# SmartIMU_I2C_Sch.net
KiCad netlist of a schematic drawn in Altium Designer
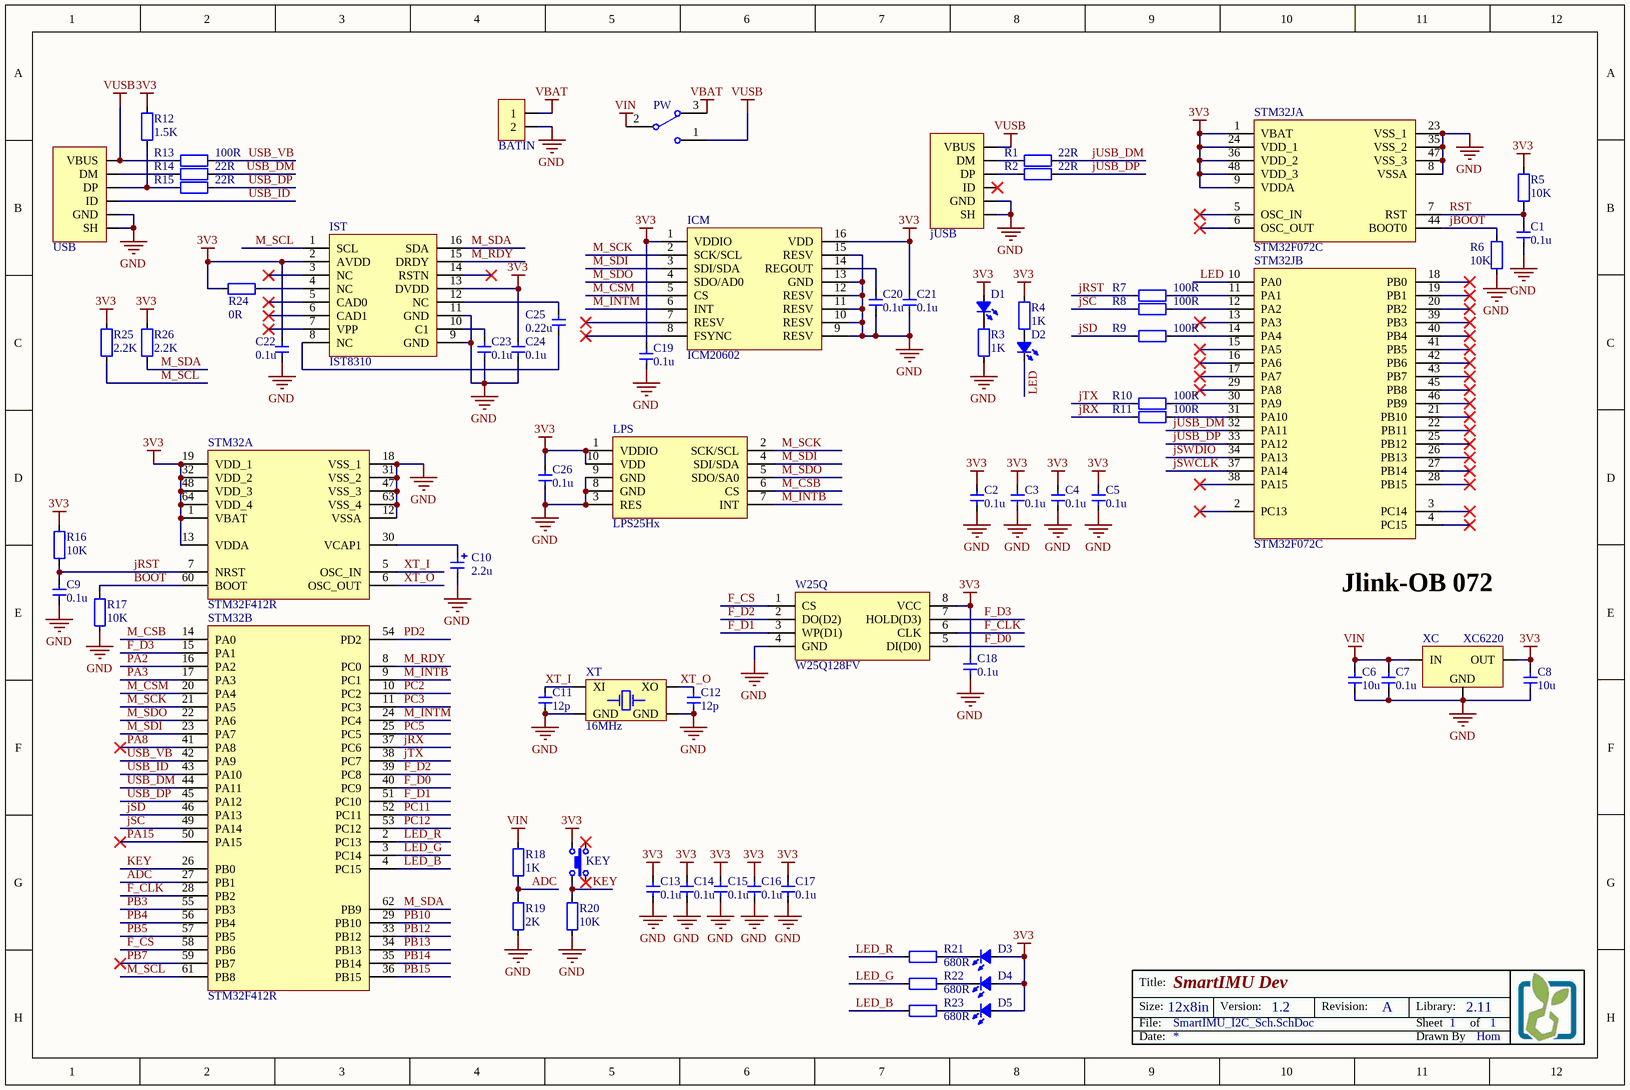
[diagram p0: SmartIMU_I2C_Sch.SchDoc]

(export (version "E")
  (design (tool "Eeschema 10.0.6"))
  (components
    (comp (ref "BATIN")
      (value "MX1.25_2P")
      (footprint "PCB_Connector:MX1.25_S90_2P")
      (description "MX")
      (libsource (lib "SCH_Connector") (part "MX1.25_2P"))
    )
    (comp (ref "C1")
      (value "0.1u")
      (footprint "PCB_PassiveCap:CAP_0603")
      (description "Capacitor")
      (fields (field (name "Comment") "Cap_0603"))
      (libsource (lib "SCH_Passive") (part "Cap_0603"))
    )
    (comp (ref "C2")
      (value "0.1u")
      (footprint "PCB_PassiveCap:CAP_0603")
      (description "Capacitor")
      (fields (field (name "Comment") "Cap_0603"))
      (libsource (lib "SCH_Passive") (part "Cap_0603"))
    )
    (comp (ref "C3")
      (value "0.1u")
      (footprint "PCB_PassiveCap:CAP_0603")
      (description "Capacitor")
      (fields (field (name "Comment") "Cap_0603"))
      (libsource (lib "SCH_Passive") (part "Cap_0603"))
    )
    (comp (ref "C4")
      (value "0.1u")
      (footprint "PCB_PassiveCap:CAP_0603")
      (description "Capacitor")
      (fields (field (name "Comment") "Cap_0603"))
      (libsource (lib "SCH_Passive") (part "Cap_0603"))
    )
    (comp (ref "C5")
      (value "0.1u")
      (footprint "PCB_PassiveCap:CAP_0603")
      (description "Capacitor")
      (fields (field (name "Comment") "Cap_0603"))
      (libsource (lib "SCH_Passive") (part "Cap_0603"))
    )
    (comp (ref "C6")
      (value "10u")
      (footprint "PCB_PassiveCap:CAP_0603")
      (description "Capacitor")
      (fields (field (name "Comment") "Cap_0603"))
      (libsource (lib "SCH_Passive") (part "Cap_0603"))
    )
    (comp (ref "C7")
      (value "0.1u")
      (footprint "PCB_PassiveCap:CAP_0603")
      (description "Capacitor")
      (fields (field (name "Comment") "Cap_0603"))
      (libsource (lib "SCH_Passive") (part "Cap_0603"))
    )
    (comp (ref "C8")
      (value "10u")
      (footprint "PCB_PassiveCap:CAP_0603")
      (description "Capacitor")
      (fields (field (name "Comment") "Cap_0603"))
      (libsource (lib "SCH_Passive") (part "Cap_0603"))
    )
    (comp (ref "C9")
      (value "0.1u")
      (footprint "PCB_PassiveCap:CAP_0603")
      (description "Capacitor")
      (fields (field (name "Comment") "Cap_0603"))
      (libsource (lib "SCH_Passive") (part "Cap_0603"))
    )
    (comp (ref "C10")
      (value "2.2u")
      (footprint "PCB_PassiveCap:CAP_TAN_P0805")
      (description "Capacitor")
      (fields (field (name "Comment") "Cap_Tan_0805"))
      (libsource (lib "SCH_Passive") (part "Cap_Tan_0805"))
    )
    (comp (ref "C11")
      (value "12p")
      (footprint "PCB_PassiveCap:CAP_0603")
      (description "Capacitor")
      (fields (field (name "Comment") "Cap_0603"))
      (libsource (lib "SCH_Passive") (part "Cap_0603"))
    )
    (comp (ref "C12")
      (value "12p")
      (footprint "PCB_PassiveCap:CAP_0603")
      (description "Capacitor")
      (fields (field (name "Comment") "Cap_0603"))
      (libsource (lib "SCH_Passive") (part "Cap_0603"))
    )
    (comp (ref "C13")
      (value "0.1u")
      (footprint "PCB_PassiveCap:CAP_0603")
      (description "Capacitor")
      (fields (field (name "Comment") "Cap_0603"))
      (libsource (lib "SCH_Passive") (part "Cap_0603"))
    )
    (comp (ref "C14")
      (value "0.1u")
      (footprint "PCB_PassiveCap:CAP_0603")
      (description "Capacitor")
      (fields (field (name "Comment") "Cap_0603"))
      (libsource (lib "SCH_Passive") (part "Cap_0603"))
    )
    (comp (ref "C15")
      (value "0.1u")
      (footprint "PCB_PassiveCap:CAP_0603")
      (description "Capacitor")
      (fields (field (name "Comment") "Cap_0603"))
      (libsource (lib "SCH_Passive") (part "Cap_0603"))
    )
    (comp (ref "C16")
      (value "0.1u")
      (footprint "PCB_PassiveCap:CAP_0603")
      (description "Capacitor")
      (fields (field (name "Comment") "Cap_0603"))
      (libsource (lib "SCH_Passive") (part "Cap_0603"))
    )
    (comp (ref "C17")
      (value "0.1u")
      (footprint "PCB_PassiveCap:CAP_0603")
      (description "Capacitor")
      (fields (field (name "Comment") "Cap_0603"))
      (libsource (lib "SCH_Passive") (part "Cap_0603"))
    )
    (comp (ref "C18")
      (value "0.1u")
      (footprint "PCB_PassiveCap:CAP_0603")
      (description "Capacitor")
      (fields (field (name "Comment") "Cap_0603"))
      (libsource (lib "SCH_Passive") (part "Cap_0603"))
    )
    (comp (ref "C19")
      (value "0.1u")
      (footprint "PCB_PassiveCap:CAP_0603")
      (description "Capacitor")
      (fields (field (name "Comment") "Cap_0603"))
      (libsource (lib "SCH_Passive") (part "Cap_0603"))
    )
    (comp (ref "C20")
      (value "0.1u")
      (footprint "PCB_PassiveCap:CAP_0603")
      (description "Capacitor")
      (fields (field (name "Comment") "Cap_0603"))
      (libsource (lib "SCH_Passive") (part "Cap_0603"))
    )
    (comp (ref "C21")
      (value "0.1u")
      (footprint "PCB_PassiveCap:CAP_0603")
      (description "Capacitor")
      (fields (field (name "Comment") "Cap_0603"))
      (libsource (lib "SCH_Passive") (part "Cap_0603"))
    )
    (comp (ref "C22")
      (value "0.1u")
      (footprint "PCB_PassiveCap:CAP_0603")
      (description "Capacitor")
      (fields (field (name "Comment") "Cap_0603"))
      (libsource (lib "SCH_Passive") (part "Cap_0603"))
    )
    (comp (ref "C23")
      (value "0.1u")
      (footprint "PCB_PassiveCap:CAP_0603")
      (description "Capacitor")
      (fields (field (name "Comment") "Cap_0603"))
      (libsource (lib "SCH_Passive") (part "Cap_0603"))
    )
    (comp (ref "C24")
      (value "0.1u")
      (footprint "PCB_PassiveCap:CAP_0603")
      (description "Capacitor")
      (fields (field (name "Comment") "Cap_0603"))
      (libsource (lib "SCH_Passive") (part "Cap_0603"))
    )
    (comp (ref "C25")
      (value "0.22u")
      (footprint "PCB_PassiveCap:CAP_0603")
      (description "Capacitor")
      (fields (field (name "Comment") "Cap_0603"))
      (libsource (lib "SCH_Passive") (part "Cap_0603"))
    )
    (comp (ref "C26")
      (value "0.1u")
      (footprint "PCB_PassiveCap:CAP_0603")
      (description "Capacitor")
      (fields (field (name "Comment") "Cap_0603"))
      (libsource (lib "SCH_Passive") (part "Cap_0603"))
    )
    (comp (ref "D1")
      (value "LED_0603")
      (footprint "PCB_ActiveLED:LED_0603_YELLOW")
      (description "LED")
      (libsource (lib "SCH_Active") (part "LED_0603"))
    )
    (comp (ref "D2")
      (value "LED_0603")
      (footprint "PCB_ActiveLED:LED_0603_ORANGE")
      (description "LED")
      (libsource (lib "SCH_Active") (part "LED_0603"))
    )
    (comp (ref "D3")
      (value "LED_0603")
      (footprint "PCB_ActiveLED:LED_0603_RED")
      (description "LED")
      (libsource (lib "SCH_Active") (part "LED_0603"))
    )
    (comp (ref "D4")
      (value "LED_0603")
      (footprint "PCB_ActiveLED:LED_0603_GREEN")
      (description "LED")
      (libsource (lib "SCH_Active") (part "LED_0603"))
    )
    (comp (ref "D5")
      (value "LED_0603")
      (footprint "PCB_ActiveLED:LED_0603_BLUE")
      (description "LED")
      (libsource (lib "SCH_Active") (part "LED_0603"))
    )
    (comp (ref "ICM")
      (value "ICM20602")
      (footprint "LGA_P0.5_16")
      (description "Sensor Motion")
      (libsource (lib "SCH_IntegratedCircuit") (part "ICM20602"))
    )
    (comp (ref "IST")
      (value "IST8310")
      (footprint "PCB_IntegratedCircuit:QFN_P0.5_16")
      (description "Sensor Magnetometer")
      (libsource (lib "SCH_IntegratedCircuit") (part "IST8310"))
    )
    (comp (ref "jUSB")
      (value "USB_Micro")
      (footprint "PCB_USB:USB_Micro-AB")
      (description "USB")
      (libsource (lib "SCH_USB") (part "USB_Micro"))
    )
    (comp (ref "KEY")
      (value "ButtonTACT")
      (footprint "PCB_Switch:ButtonTACT_3.5*3.55_90")
      (description "Button")
      (libsource (lib "SCH_Switch") (part "ButtonTACT"))
    )
    (comp (ref "LPS")
      (value "LPS25Hx")
      (footprint "PCB_IntegratedCircuit:HCLGA-2.5x2.5_10")
      (description "Sensor Pressure")
      (libsource (lib "SCH_IntegratedCircuit") (part "LPS25Hx"))
    )
    (comp (ref "PW")
      (value "SwitchSPDT_2.8x6.6_90")
      (footprint "PCB_Switch:SwitchSPDT_2.8X6.6_90")
      (description "Switch")
      (libsource (lib "SCH_Switch") (part "SwitchSPDT_2.8x6.6_90"))
    )
    (comp (ref "R1")
      (value "22R")
      (footprint "PCB_PassiveRes:RES_0603")
      (description "Resistor")
      (fields (field (name "Comment") "Res_0603"))
      (libsource (lib "") (part "Res_0603_2"))
    )
    (comp (ref "R2")
      (value "22R")
      (footprint "PCB_PassiveRes:RES_0603")
      (description "Resistor")
      (fields (field (name "Comment") "Res_0603"))
      (libsource (lib "") (part "Res_0603_2"))
    )
    (comp (ref "R3")
      (value "1K")
      (footprint "PCB_PassiveRes:RES_0603")
      (description "Resistor")
      (fields (field (name "Comment") "Res_0603"))
      (libsource (lib "") (part "Res_0603_3"))
    )
    (comp (ref "R4")
      (value "1K")
      (footprint "PCB_PassiveRes:RES_0603")
      (description "Resistor")
      (fields (field (name "Comment") "Res_0603"))
      (libsource (lib "") (part "Res_0603_3"))
    )
    (comp (ref "R5")
      (value "10K")
      (footprint "PCB_PassiveRes:RES_0603")
      (description "Resistor")
      (fields (field (name "Comment") "Res_0603"))
      (libsource (lib "") (part "Res_0603_3"))
    )
    (comp (ref "R6")
      (value "10K")
      (footprint "PCB_PassiveRes:RES_0603")
      (description "Resistor")
      (fields (field (name "Comment") "Res_0603"))
      (libsource (lib "") (part "Res_0603_3"))
    )
    (comp (ref "R7")
      (value "100R")
      (footprint "PCB_PassiveRes:RES_0603")
      (description "Resistor")
      (fields (field (name "Comment") "Res_0603"))
      (libsource (lib "") (part "Res_0603_2"))
    )
    (comp (ref "R8")
      (value "100R")
      (footprint "PCB_PassiveRes:RES_0603")
      (description "Resistor")
      (fields (field (name "Comment") "Res_0603"))
      (libsource (lib "") (part "Res_0603_2"))
    )
    (comp (ref "R9")
      (value "100R")
      (footprint "PCB_PassiveRes:RES_0603")
      (description "Resistor")
      (fields (field (name "Comment") "Res_0603"))
      (libsource (lib "") (part "Res_0603_2"))
    )
    (comp (ref "R10")
      (value "100R")
      (footprint "PCB_PassiveRes:RES_0603")
      (description "Resistor")
      (fields (field (name "Comment") "Res_0603"))
      (libsource (lib "") (part "Res_0603_2"))
    )
    (comp (ref "R11")
      (value "100R")
      (footprint "PCB_PassiveRes:RES_0603")
      (description "Resistor")
      (fields (field (name "Comment") "Res_0603"))
      (libsource (lib "") (part "Res_0603_2"))
    )
    (comp (ref "R12")
      (value "1.5K")
      (footprint "PCB_PassiveRes:RES_0603")
      (description "Resistor")
      (fields (field (name "Comment") "Res_0603"))
      (libsource (lib "SCH_Passive") (part "Res_0603"))
    )
    (comp (ref "R13")
      (value "100R")
      (footprint "PCB_PassiveRes:RES_0603")
      (description "Resistor")
      (fields (field (name "Comment") "Res_0603"))
      (libsource (lib "") (part "Res_0603_1"))
    )
    (comp (ref "R14")
      (value "22R")
      (footprint "PCB_PassiveRes:RES_0603")
      (description "Resistor")
      (fields (field (name "Comment") "Res_0603"))
      (libsource (lib "") (part "Res_0603_1"))
    )
    (comp (ref "R15")
      (value "22R")
      (footprint "PCB_PassiveRes:RES_0603")
      (description "Resistor")
      (fields (field (name "Comment") "Res_0603"))
      (libsource (lib "") (part "Res_0603_1"))
    )
    (comp (ref "R16")
      (value "10K")
      (footprint "PCB_PassiveRes:RES_0603")
      (description "Resistor")
      (fields (field (name "Comment") "Res_0603"))
      (libsource (lib "") (part "Res_0603_3"))
    )
    (comp (ref "R17")
      (value "10K")
      (footprint "PCB_PassiveRes:RES_0603")
      (description "Resistor")
      (fields (field (name "Comment") "Res_0603"))
      (libsource (lib "") (part "Res_0603_3"))
    )
    (comp (ref "R18")
      (value "1K")
      (footprint "PCB_PassiveRes:RES_0603")
      (description "Resistor")
      (fields (field (name "Comment") "Res_0603"))
      (libsource (lib "SCH_Passive") (part "Res_0603"))
    )
    (comp (ref "R19")
      (value "2K")
      (footprint "PCB_PassiveRes:RES_0603")
      (description "Resistor")
      (fields (field (name "Comment") "Res_0603"))
      (libsource (lib "SCH_Passive") (part "Res_0603"))
    )
    (comp (ref "R20")
      (value "10K")
      (footprint "PCB_PassiveRes:RES_0603")
      (description "Resistor")
      (fields (field (name "Comment") "Res_0603"))
      (libsource (lib "") (part "Res_0603_3"))
    )
    (comp (ref "R21")
      (value "680R")
      (footprint "PCB_PassiveRes:RES_0603")
      (description "Resistor")
      (fields (field (name "Comment") "Res_0603"))
      (libsource (lib "") (part "Res_0603_1"))
    )
    (comp (ref "R22")
      (value "680R")
      (footprint "PCB_PassiveRes:RES_0603")
      (description "Resistor")
      (fields (field (name "Comment") "Res_0603"))
      (libsource (lib "") (part "Res_0603_1"))
    )
    (comp (ref "R23")
      (value "680R")
      (footprint "PCB_PassiveRes:RES_0603")
      (description "Resistor")
      (fields (field (name "Comment") "Res_0603"))
      (libsource (lib "") (part "Res_0603_1"))
    )
    (comp (ref "R24")
      (value "0R")
      (footprint "PCB_PassiveRes:RES_0603")
      (description "Resistor")
      (fields (field (name "Comment") "Res_0603"))
      (libsource (lib "") (part "Res_0603_1"))
    )
    (comp (ref "R25")
      (value "2.2K")
      (footprint "PCB_PassiveRes:RES_0603")
      (description "Resistor")
      (fields (field (name "Comment") "Res_0603"))
      (libsource (lib "SCH_Passive") (part "Res_0603"))
    )
    (comp (ref "R26")
      (value "2.2K")
      (footprint "PCB_PassiveRes:RES_0603")
      (description "Resistor")
      (fields (field (name "Comment") "Res_0603"))
      (libsource (lib "SCH_Passive") (part "Res_0603"))
    )
    (comp (ref "STM32")
      (value "STM32F412R")
      (footprint "PCB_IntegratedCircuit:LQFP_P0.5_64")
      (description "MCU")
      (libsource (lib "SCH_IntegratedCircuit") (part "STM32F412R/446R"))
    )
    (comp (ref "STM32J")
      (value "STM32F072C")
      (footprint "PCB_IntegratedCircuit:LQFP_P0.5_48")
      (description "MCU")
      (libsource (lib "SCH_IntegratedCircuit") (part "STM32F103C"))
    )
    (comp (ref "USB")
      (value "USB_Micro")
      (footprint "PCB_USB:USB_Micro-AB")
      (description "USB")
      (libsource (lib "SCH_USB") (part "USB_Micro"))
    )
    (comp (ref "W25Q")
      (value "W25Q128FV")
      (footprint "PCB_IntegratedCircuit:SON_P1.27H_8")
      (description "FLASH")
      (libsource (lib "SCH_IntegratedCircuit") (part "W25Q_8"))
    )
    (comp (ref "XC")
      (value "XC6220")
      (footprint "PCB_IntegratedCircuit:SOT89-3")
      (description "Power")
      (libsource (lib "SCH_IntegratedCircuit") (part "XC6220"))
    )
    (comp (ref "XT")
      (value "16MHz")
      (footprint "PCB_Oscillator:XT_2520_4")
      (description "Crystal Oscillator")
      (fields (field (name "Comment") "XTAL_2520_4P"))
      (libsource (lib "SCH_Oscillator") (part "XTAL_2520_4P"))
    )
  )
  (nets
    (net (code "1") (name "/ADC") (class "Default")
      (node (ref "R18") (pin "2") (pinfunction "2_2") (pintype "passive"))
      (node (ref "R19") (pin "1") (pinfunction "1_1") (pintype "passive"))
      (node (ref "STM32") (pin "27") (pinfunction "PB1_27") (pintype "passive"))
    )
    (net (code "2") (name "/BOOT") (class "Default")
      (node (ref "R17") (pin "2") (pinfunction "2_2") (pintype "passive"))
      (node (ref "STM32") (pin "60") (pinfunction "BOOT_60") (pintype "passive"))
    )
    (net (code "3") (name "/F_CLK") (class "Default")
      (node (ref "STM32") (pin "28") (pinfunction "PB2_28") (pintype "passive"))
      (node (ref "W25Q") (pin "6") (pinfunction "CLK_6") (pintype "passive"))
    )
    (net (code "4") (name "/F_CS") (class "Default")
      (node (ref "STM32") (pin "58") (pinfunction "PB6_58") (pintype "passive"))
      (node (ref "W25Q") (pin "1") (pinfunction "CS_1") (pintype "passive"))
    )
    (net (code "5") (name "/F_D0") (class "Default")
      (node (ref "STM32") (pin "40") (pinfunction "PC9_40") (pintype "passive"))
      (node (ref "W25Q") (pin "5") (pinfunction "DI(D0)_5") (pintype "passive"))
    )
    (net (code "6") (name "/F_D1") (class "Default")
      (node (ref "STM32") (pin "51") (pinfunction "PC10_51") (pintype "passive"))
      (node (ref "W25Q") (pin "3") (pinfunction "WP(D1)_3") (pintype "passive"))
    )
    (net (code "7") (name "/F_D2") (class "Default")
      (node (ref "STM32") (pin "39") (pinfunction "PC8_39") (pintype "passive"))
      (node (ref "W25Q") (pin "2") (pinfunction "DO(D2)_2") (pintype "passive"))
    )
    (net (code "8") (name "/F_D3") (class "Default")
      (node (ref "STM32") (pin "15") (pinfunction "PA1_15") (pintype "passive"))
      (node (ref "W25Q") (pin "7") (pinfunction "HOLD(D3)_7") (pintype "passive"))
    )
    (net (code "9") (name "/KEY") (class "Default")
      (node (ref "KEY") (pin "1") (pinfunction "1_1") (pintype "passive"))
      (node (ref "R20") (pin "2") (pinfunction "2_2") (pintype "passive"))
      (node (ref "STM32") (pin "26") (pinfunction "PB0_26") (pintype "passive"))
    )
    (net (code "10") (name "/LED") (class "Default")
      (node (ref "D2") (pin "2") (pinfunction "K_2") (pintype "passive"))
      (node (ref "STM32J") (pin "10") (pinfunction "PA0_10") (pintype "passive"))
    )
    (net (code "11") (name "/LED_B") (class "Default")
      (node (ref "R23") (pin "2") (pinfunction "2_2") (pintype "passive"))
      (node (ref "STM32") (pin "4") (pinfunction "PC15_4") (pintype "passive"))
    )
    (net (code "12") (name "/LED_G") (class "Default")
      (node (ref "R22") (pin "2") (pinfunction "2_2") (pintype "passive"))
      (node (ref "STM32") (pin "3") (pinfunction "PC14_3") (pintype "passive"))
    )
    (net (code "13") (name "/LED_R") (class "Default")
      (node (ref "R21") (pin "2") (pinfunction "2_2") (pintype "passive"))
      (node (ref "STM32") (pin "2") (pinfunction "PC13_2") (pintype "passive"))
    )
    (net (code "14") (name "/M_CSB") (class "Default")
      (node (ref "LPS") (pin "6") (pinfunction "CS_6") (pintype "passive"))
      (node (ref "STM32") (pin "14") (pinfunction "PA0_14") (pintype "passive"))
    )
    (net (code "15") (name "/M_CSM") (class "Default")
      (node (ref "ICM") (pin "5") (pinfunction "CS_5") (pintype "passive"))
      (node (ref "STM32") (pin "20") (pinfunction "PA4_20") (pintype "passive"))
    )
    (net (code "16") (name "/M_INTB") (class "Default")
      (node (ref "LPS") (pin "7") (pinfunction "INT_7") (pintype "passive"))
      (node (ref "STM32") (pin "9") (pinfunction "PC1_9") (pintype "passive"))
    )
    (net (code "17") (name "/M_INTM") (class "Default")
      (node (ref "ICM") (pin "6") (pinfunction "INT_6") (pintype "passive"))
      (node (ref "STM32") (pin "24") (pinfunction "PC4_24") (pintype "passive"))
    )
    (net (code "18") (name "/M_RDY") (class "Default")
      (node (ref "IST") (pin "15") (pinfunction "DRDY_15") (pintype "passive"))
      (node (ref "STM32") (pin "8") (pinfunction "PC0_8") (pintype "passive"))
    )
    (net (code "19") (name "/M_SCK") (class "Default")
      (node (ref "ICM") (pin "2") (pinfunction "SCK/SCL_2") (pintype "passive"))
      (node (ref "LPS") (pin "2") (pinfunction "SCK/SCL_2") (pintype "passive"))
      (node (ref "STM32") (pin "21") (pinfunction "PA5_21") (pintype "passive"))
    )
    (net (code "20") (name "/M_SCL") (class "Default")
      (node (ref "IST") (pin "1") (pinfunction "SCL_1") (pintype "passive"))
      (node (ref "R25") (pin "2") (pinfunction "2_2") (pintype "passive"))
      (node (ref "STM32") (pin "61") (pinfunction "PB8_61") (pintype "passive"))
    )
    (net (code "21") (name "/M_SDA") (class "Default")
      (node (ref "IST") (pin "16") (pinfunction "SDA_16") (pintype "passive"))
      (node (ref "R26") (pin "2") (pinfunction "2_2") (pintype "passive"))
      (node (ref "STM32") (pin "62") (pinfunction "PB9_62") (pintype "passive"))
    )
    (net (code "22") (name "/M_SDI") (class "Default")
      (node (ref "ICM") (pin "3") (pinfunction "SDI/SDA_3") (pintype "passive"))
      (node (ref "LPS") (pin "4") (pinfunction "SDI/SDA_4") (pintype "passive"))
      (node (ref "STM32") (pin "23") (pinfunction "PA7_23") (pintype "passive"))
    )
    (net (code "23") (name "/M_SDO") (class "Default")
      (node (ref "ICM") (pin "4") (pinfunction "SDO/AD0_4") (pintype "passive"))
      (node (ref "LPS") (pin "5") (pinfunction "SDO/SA0_5") (pintype "passive"))
      (node (ref "STM32") (pin "22") (pinfunction "PA6_22") (pintype "passive"))
    )
    (net (code "24") (name "/PA2") (class "Default")
      (node (ref "STM32") (pin "16") (pinfunction "PA2_16") (pintype "passive"))
    )
    (net (code "25") (name "/PA3") (class "Default")
      (node (ref "STM32") (pin "17") (pinfunction "PA3_17") (pintype "passive"))
    )
    (net (code "26") (name "/PA8") (class "Default")
      (node (ref "STM32") (pin "41") (pinfunction "PA8_41") (pintype "passive+no_connect"))
    )
    (net (code "27") (name "/PA15") (class "Default")
      (node (ref "STM32") (pin "50") (pinfunction "PA15_50") (pintype "passive+no_connect"))
    )
    (net (code "28") (name "/PB3") (class "Default")
      (node (ref "STM32") (pin "55") (pinfunction "PB3_55") (pintype "passive"))
    )
    (net (code "29") (name "/PB4") (class "Default")
      (node (ref "STM32") (pin "56") (pinfunction "PB4_56") (pintype "passive"))
    )
    (net (code "30") (name "/PB5") (class "Default")
      (node (ref "STM32") (pin "57") (pinfunction "PB5_57") (pintype "passive"))
    )
    (net (code "31") (name "/PB7") (class "Default")
      (node (ref "STM32") (pin "59") (pinfunction "PB7_59") (pintype "passive+no_connect"))
    )
    (net (code "32") (name "/PB10") (class "Default")
      (node (ref "STM32") (pin "29") (pinfunction "PB10_29") (pintype "passive"))
    )
    (net (code "33") (name "/PB12") (class "Default")
      (node (ref "STM32") (pin "33") (pinfunction "PB12_33") (pintype "passive"))
    )
    (net (code "34") (name "/PB13") (class "Default")
      (node (ref "STM32") (pin "34") (pinfunction "PB13_34") (pintype "passive"))
    )
    (net (code "35") (name "/PB14") (class "Default")
      (node (ref "STM32") (pin "35") (pinfunction "PB14_35") (pintype "passive"))
    )
    (net (code "36") (name "/PB15") (class "Default")
      (node (ref "STM32") (pin "36") (pinfunction "PB15_36") (pintype "passive"))
    )
    (net (code "37") (name "/PC2") (class "Default")
      (node (ref "STM32") (pin "10") (pinfunction "PC2_10") (pintype "passive"))
    )
    (net (code "38") (name "/PC3") (class "Default")
      (node (ref "STM32") (pin "11") (pinfunction "PC3_11") (pintype "passive"))
    )
    (net (code "39") (name "/PC5") (class "Default")
      (node (ref "STM32") (pin "25") (pinfunction "PC5_25") (pintype "passive"))
    )
    (net (code "40") (name "/PC11") (class "Default")
      (node (ref "STM32") (pin "52") (pinfunction "PC11_52") (pintype "passive"))
    )
    (net (code "41") (name "/PC12") (class "Default")
      (node (ref "STM32") (pin "53") (pinfunction "PC12_53") (pintype "passive"))
    )
    (net (code "42") (name "/PD2") (class "Default")
      (node (ref "STM32") (pin "54") (pinfunction "PD2_54") (pintype "passive"))
    )
    (net (code "43") (name "/RST") (class "Default")
      (node (ref "C1") (pin "2") (pinfunction "2_2") (pintype "passive"))
      (node (ref "R5") (pin "1") (pinfunction "1_1") (pintype "passive"))
      (node (ref "STM32J") (pin "7") (pinfunction "RST_7") (pintype "passive"))
    )
    (net (code "44") (name "/USB_DM") (class "Default")
      (node (ref "R14") (pin "1") (pinfunction "1_1") (pintype "passive"))
      (node (ref "STM32") (pin "44") (pinfunction "PA11_44") (pintype "passive"))
    )
    (net (code "45") (name "/USB_DP") (class "Default")
      (node (ref "R15") (pin "1") (pinfunction "1_1") (pintype "passive"))
      (node (ref "STM32") (pin "45") (pinfunction "PA12_45") (pintype "passive"))
    )
    (net (code "46") (name "/USB_ID") (class "Default")
      (node (ref "STM32") (pin "43") (pinfunction "PA10_43") (pintype "passive"))
      (node (ref "USB") (pin "4") (pinfunction "ID_4") (pintype "passive"))
    )
    (net (code "47") (name "/USB_VB") (class "Default")
      (node (ref "R13") (pin "1") (pinfunction "1_1") (pintype "passive"))
      (node (ref "STM32") (pin "42") (pinfunction "PA9_42") (pintype "passive"))
    )
    (net (code "48") (name "/XT_I") (class "Default")
      (node (ref "C11") (pin "1") (pinfunction "1_1") (pintype "passive"))
      (node (ref "STM32") (pin "5") (pinfunction "OSC_IN_5") (pintype "passive"))
      (node (ref "XT") (pin "1") (pinfunction "XI_1") (pintype "passive"))
    )
    (net (code "49") (name "/XT_O") (class "Default")
      (node (ref "C12") (pin "1") (pinfunction "1_1") (pintype "passive"))
      (node (ref "STM32") (pin "6") (pinfunction "OSC_OUT_6") (pintype "passive"))
      (node (ref "XT") (pin "3") (pinfunction "XO_3") (pintype "passive"))
    )
    (net (code "50") (name "/jBOOT") (class "Default")
      (node (ref "R6") (pin "2") (pinfunction "2_2") (pintype "passive"))
      (node (ref "STM32J") (pin "44") (pinfunction "BOOT0_44") (pintype "passive"))
    )
    (net (code "51") (name "/jRST") (class "Default")
      (node (ref "C9") (pin "2") (pinfunction "2_2") (pintype "passive"))
      (node (ref "R16") (pin "1") (pinfunction "1_1") (pintype "passive"))
      (node (ref "R7") (pin "1") (pinfunction "1_1") (pintype "passive"))
      (node (ref "STM32") (pin "7") (pinfunction "NRST_7") (pintype "passive"))
    )
    (net (code "52") (name "/jRX") (class "Default")
      (node (ref "R11") (pin "1") (pinfunction "1_1") (pintype "passive"))
      (node (ref "STM32") (pin "37") (pinfunction "PC6_37") (pintype "passive"))
    )
    (net (code "53") (name "/jSC") (class "Default")
      (node (ref "R8") (pin "1") (pinfunction "1_1") (pintype "passive"))
      (node (ref "STM32") (pin "49") (pinfunction "PA14_49") (pintype "passive"))
    )
    (net (code "54") (name "/jSD") (class "Default")
      (node (ref "R9") (pin "1") (pinfunction "1_1") (pintype "passive"))
      (node (ref "STM32") (pin "46") (pinfunction "PA13_46") (pintype "passive"))
    )
    (net (code "55") (name "/jSWCLK") (class "Default")
      (node (ref "STM32J") (pin "37") (pinfunction "PA14_37") (pintype "passive"))
    )
    (net (code "56") (name "/jSWDIO") (class "Default")
      (node (ref "STM32J") (pin "34") (pinfunction "PA13_34") (pintype "passive"))
    )
    (net (code "57") (name "/jTX") (class "Default")
      (node (ref "R10") (pin "1") (pinfunction "1_1") (pintype "passive"))
      (node (ref "STM32") (pin "38") (pinfunction "PC7_38") (pintype "passive"))
    )
    (net (code "58") (name "/jUSB_DM") (class "Default")
      (node (ref "R1") (pin "2") (pinfunction "2_2") (pintype "passive"))
      (node (ref "STM32J") (pin "32") (pinfunction "PA11_32") (pintype "passive"))
    )
    (net (code "59") (name "/jUSB_DP") (class "Default")
      (node (ref "R2") (pin "2") (pinfunction "2_2") (pintype "passive"))
      (node (ref "STM32J") (pin "33") (pinfunction "PA12_33") (pintype "passive"))
    )
    (net (code "60") (name "3V3") (class "Default")
      (node (ref "C13") (pin "1") (pinfunction "1_1") (pintype "passive"))
      (node (ref "C14") (pin "1") (pinfunction "1_1") (pintype "passive"))
      (node (ref "C15") (pin "1") (pinfunction "1_1") (pintype "passive"))
      (node (ref "C16") (pin "1") (pinfunction "1_1") (pintype "passive"))
      (node (ref "C17") (pin "2") (pinfunction "2_2") (pintype "passive"))
      (node (ref "C18") (pin "1") (pinfunction "1_1") (pintype "passive"))
      (node (ref "C19") (pin "1") (pinfunction "1_1") (pintype "passive"))
      (node (ref "C2") (pin "2") (pinfunction "2_2") (pintype "passive"))
      (node (ref "C21") (pin "1") (pinfunction "1_1") (pintype "passive"))
      (node (ref "C22") (pin "1") (pinfunction "1_1") (pintype "passive"))
      (node (ref "C24") (pin "1") (pinfunction "1_1") (pintype "passive"))
      (node (ref "C26") (pin "1") (pinfunction "1_1") (pintype "passive"))
      (node (ref "C3") (pin "2") (pinfunction "2_2") (pintype "passive"))
      (node (ref "C4") (pin "2") (pinfunction "2_2") (pintype "passive"))
      (node (ref "C5") (pin "2") (pinfunction "2_2") (pintype "passive"))
      (node (ref "C8") (pin "2") (pinfunction "2_2") (pintype "passive"))
      (node (ref "D1") (pin "1") (pinfunction "A_1") (pintype "passive"))
      (node (ref "D3") (pin "1") (pinfunction "A_1") (pintype "passive"))
      (node (ref "D4") (pin "1") (pinfunction "A_1") (pintype "passive"))
      (node (ref "D5") (pin "1") (pinfunction "A_1") (pintype "passive"))
      (node (ref "ICM") (pin "1") (pinfunction "VDDIO_1") (pintype "passive"))
      (node (ref "ICM") (pin "16") (pinfunction "VDD_16") (pintype "passive"))
      (node (ref "IST") (pin "13") (pinfunction "DVDD_13") (pintype "passive"))
      (node (ref "IST") (pin "2") (pinfunction "AVDD_2") (pintype "passive"))
      (node (ref "KEY") (pin "2") (pinfunction "2_2") (pintype "passive"))
      (node (ref "LPS") (pin "1") (pinfunction "VDDIO_1") (pintype "passive"))
      (node (ref "LPS") (pin "10") (pinfunction "VDD_10") (pintype "passive"))
      (node (ref "R12") (pin "1") (pinfunction "1_1") (pintype "passive"))
      (node (ref "R16") (pin "2") (pinfunction "2_2") (pintype "passive"))
      (node (ref "R24") (pin "2") (pinfunction "2_2") (pintype "passive"))
      (node (ref "R25") (pin "1") (pinfunction "1_1") (pintype "passive"))
      (node (ref "R26") (pin "1") (pinfunction "1_1") (pintype "passive"))
      (node (ref "R4") (pin "2") (pinfunction "2_2") (pintype "passive"))
      (node (ref "R5") (pin "2") (pinfunction "2_2") (pintype "passive"))
      (node (ref "STM32") (pin "1") (pinfunction "VBAT_1") (pintype "passive"))
      (node (ref "STM32") (pin "13") (pinfunction "VDDA_13") (pintype "passive"))
      (node (ref "STM32") (pin "19") (pinfunction "VDD_1_19") (pintype "passive"))
      (node (ref "STM32") (pin "32") (pinfunction "VDD_2_32") (pintype "passive"))
      (node (ref "STM32") (pin "48") (pinfunction "VDD_3_48") (pintype "passive"))
      (node (ref "STM32") (pin "64") (pinfunction "VDD_4_64") (pintype "passive"))
      (node (ref "STM32J") (pin "1") (pinfunction "VBAT_1") (pintype "passive"))
      (node (ref "STM32J") (pin "24") (pinfunction "VDD_1_24") (pintype "passive"))
      (node (ref "STM32J") (pin "36") (pinfunction "VDD_2_36") (pintype "passive"))
      (node (ref "STM32J") (pin "48") (pinfunction "VDD_3_48") (pintype "passive"))
      (node (ref "STM32J") (pin "9") (pinfunction "VDDA_9") (pintype "passive"))
      (node (ref "W25Q") (pin "8") (pinfunction "VCC_8") (pintype "passive"))
      (node (ref "XC") (pin "2") (pinfunction "OUT_2") (pintype "power_in"))
    )
    (net (code "61") (name "GND") (class "Default")
      (node (ref "BATIN") (pin "2") (pinfunction "2_2") (pintype "passive"))
      (node (ref "C1") (pin "1") (pinfunction "1_1") (pintype "passive"))
      (node (ref "C10") (pin "2") (pinfunction "2_2") (pintype "passive"))
      (node (ref "C11") (pin "2") (pinfunction "2_2") (pintype "passive"))
      (node (ref "C12") (pin "2") (pinfunction "2_2") (pintype "passive"))
      (node (ref "C13") (pin "2") (pinfunction "2_2") (pintype "passive"))
      (node (ref "C14") (pin "2") (pinfunction "2_2") (pintype "passive"))
      (node (ref "C15") (pin "2") (pinfunction "2_2") (pintype "passive"))
      (node (ref "C16") (pin "2") (pinfunction "2_2") (pintype "passive"))
      (node (ref "C17") (pin "1") (pinfunction "1_1") (pintype "passive"))
      (node (ref "C18") (pin "2") (pinfunction "2_2") (pintype "passive"))
      (node (ref "C19") (pin "2") (pinfunction "2_2") (pintype "passive"))
      (node (ref "C2") (pin "1") (pinfunction "1_1") (pintype "passive"))
      (node (ref "C20") (pin "2") (pinfunction "2_2") (pintype "passive"))
      (node (ref "C21") (pin "2") (pinfunction "2_2") (pintype "passive"))
      (node (ref "C22") (pin "2") (pinfunction "2_2") (pintype "passive"))
      (node (ref "C23") (pin "2") (pinfunction "2_2") (pintype "passive"))
      (node (ref "C24") (pin "2") (pinfunction "2_2") (pintype "passive"))
      (node (ref "C26") (pin "2") (pinfunction "2_2") (pintype "passive"))
      (node (ref "C3") (pin "1") (pinfunction "1_1") (pintype "passive"))
      (node (ref "C4") (pin "1") (pinfunction "1_1") (pintype "passive"))
      (node (ref "C5") (pin "1") (pinfunction "1_1") (pintype "passive"))
      (node (ref "C6") (pin "1") (pinfunction "1_1") (pintype "passive"))
      (node (ref "C7") (pin "1") (pinfunction "1_1") (pintype "passive"))
      (node (ref "C8") (pin "1") (pinfunction "1_1") (pintype "passive"))
      (node (ref "C9") (pin "1") (pinfunction "1_1") (pintype "passive"))
      (node (ref "ICM") (pin "10") (pinfunction "RESV_10") (pintype "passive"))
      (node (ref "ICM") (pin "11") (pinfunction "RESV_11") (pintype "passive"))
      (node (ref "ICM") (pin "12") (pinfunction "RESV_12") (pintype "passive"))
      (node (ref "ICM") (pin "13") (pinfunction "GND_13") (pintype "passive"))
      (node (ref "ICM") (pin "15") (pinfunction "RESV_15") (pintype "passive"))
      (node (ref "ICM") (pin "9") (pinfunction "RESV_9") (pintype "passive"))
      (node (ref "IST") (pin "11") (pinfunction "GND_11") (pintype "passive"))
      (node (ref "IST") (pin "9") (pinfunction "GND_9") (pintype "passive"))
      (node (ref "LPS") (pin "3") (pinfunction "RES_3") (pintype "passive"))
      (node (ref "LPS") (pin "8") (pinfunction "GND_8") (pintype "passive"))
      (node (ref "LPS") (pin "9") (pinfunction "GND_9") (pintype "passive"))
      (node (ref "R17") (pin "1") (pinfunction "1_1") (pintype "passive"))
      (node (ref "R19") (pin "2") (pinfunction "2_2") (pintype "passive"))
      (node (ref "R20") (pin "1") (pinfunction "1_1") (pintype "passive"))
      (node (ref "R3") (pin "1") (pinfunction "1_1") (pintype "passive"))
      (node (ref "R6") (pin "1") (pinfunction "1_1") (pintype "passive"))
      (node (ref "STM32") (pin "12") (pinfunction "VSSA_12") (pintype "passive"))
      (node (ref "STM32") (pin "18") (pinfunction "VSS_1_18") (pintype "passive"))
      (node (ref "STM32") (pin "31") (pinfunction "VSS_2_31") (pintype "passive"))
      (node (ref "STM32") (pin "47") (pinfunction "VSS_3_47") (pintype "passive"))
      (node (ref "STM32") (pin "63") (pinfunction "VSS_4_63") (pintype "passive"))
      (node (ref "STM32J") (pin "23") (pinfunction "VSS_1_23") (pintype "passive"))
      (node (ref "STM32J") (pin "35") (pinfunction "VSS_2_35") (pintype "passive"))
      (node (ref "STM32J") (pin "47") (pinfunction "VSS_3_47") (pintype "passive"))
      (node (ref "STM32J") (pin "8") (pinfunction "VSSA_8") (pintype "passive"))
      (node (ref "USB") (pin "0") (pinfunction "SH_0") (pintype "passive"))
      (node (ref "USB") (pin "5") (pinfunction "GND_5") (pintype "passive"))
      (node (ref "W25Q") (pin "4") (pinfunction "GND_4") (pintype "passive"))
      (node (ref "XC") (pin "1") (pinfunction "GND_1") (pintype "power_in"))
      (node (ref "XT") (pin "2") (pinfunction "GND_2") (pintype "passive"))
      (node (ref "XT") (pin "4") (pinfunction "GND_4") (pintype "passive"))
      (node (ref "jUSB") (pin "0") (pinfunction "SH_0") (pintype "passive"))
      (node (ref "jUSB") (pin "5") (pinfunction "GND_5") (pintype "passive"))
    )
    (net (code "62") (name "Net-(C25-Pad1)") (class "Default")
      (node (ref "C25") (pin "1") (pinfunction "1_1") (pintype "passive"))
      (node (ref "IST") (pin "12") (pinfunction "NC_12") (pintype "passive"))
    )
    (net (code "63") (name "Net-(C25-Pad2)") (class "Default")
      (node (ref "C25") (pin "2") (pinfunction "2_2") (pintype "passive"))
      (node (ref "IST") (pin "8") (pinfunction "NC_8") (pintype "passive"))
    )
    (net (code "64") (name "Net-(D1-K)") (class "Default")
      (node (ref "D1") (pin "2") (pinfunction "K_2") (pintype "passive"))
      (node (ref "R3") (pin "2") (pinfunction "2_2") (pintype "passive"))
    )
    (net (code "65") (name "Net-(D2-A)") (class "Default")
      (node (ref "D2") (pin "1") (pinfunction "A_1") (pintype "passive"))
      (node (ref "R4") (pin "1") (pinfunction "1_1") (pintype "passive"))
    )
    (net (code "66") (name "Net-(D3-K)") (class "Default")
      (node (ref "D3") (pin "2") (pinfunction "K_2") (pintype "passive"))
      (node (ref "R21") (pin "1") (pinfunction "1_1") (pintype "passive"))
    )
    (net (code "67") (name "Net-(D4-K)") (class "Default")
      (node (ref "D4") (pin "2") (pinfunction "K_2") (pintype "passive"))
      (node (ref "R22") (pin "1") (pinfunction "1_1") (pintype "passive"))
    )
    (net (code "68") (name "Net-(D5-K)") (class "Default")
      (node (ref "D5") (pin "2") (pinfunction "K_2") (pintype "passive"))
      (node (ref "R23") (pin "1") (pinfunction "1_1") (pintype "passive"))
    )
    (net (code "69") (name "Net-(ICM-REGOUT)") (class "Default")
      (node (ref "C20") (pin "1") (pinfunction "1_1") (pintype "passive"))
      (node (ref "ICM") (pin "14") (pinfunction "REGOUT_14") (pintype "passive"))
    )
    (net (code "70") (name "Net-(IST-C1)") (class "Default")
      (node (ref "C23") (pin "1") (pinfunction "1_1") (pintype "passive"))
      (node (ref "IST") (pin "10") (pinfunction "C1_10") (pintype "passive"))
    )
    (net (code "71") (name "Net-(IST-NC-Pad4)") (class "Default")
      (node (ref "IST") (pin "4") (pinfunction "NC_4") (pintype "passive"))
      (node (ref "R24") (pin "1") (pinfunction "1_1") (pintype "passive"))
    )
    (net (code "72") (name "Net-(STM32A-VCAP1)") (class "Default")
      (node (ref "C10") (pin "1") (pinfunction "1_1") (pintype "passive"))
      (node (ref "STM32") (pin "30") (pinfunction "VCAP1_30") (pintype "passive"))
    )
    (net (code "73") (name "Net-(STM32JB-PA1)") (class "Default")
      (node (ref "R7") (pin "2") (pinfunction "2_2") (pintype "passive"))
      (node (ref "STM32J") (pin "11") (pinfunction "PA1_11") (pintype "passive"))
    )
    (net (code "74") (name "Net-(STM32JB-PA2)") (class "Default")
      (node (ref "R8") (pin "2") (pinfunction "2_2") (pintype "passive"))
      (node (ref "STM32J") (pin "12") (pinfunction "PA2_12") (pintype "passive"))
    )
    (net (code "75") (name "Net-(STM32JB-PA4)") (class "Default")
      (node (ref "R9") (pin "2") (pinfunction "2_2") (pintype "passive"))
      (node (ref "STM32J") (pin "14") (pinfunction "PA4_14") (pintype "passive"))
    )
    (net (code "76") (name "Net-(STM32JB-PA9)") (class "Default")
      (node (ref "R10") (pin "2") (pinfunction "2_2") (pintype "passive"))
      (node (ref "STM32J") (pin "30") (pinfunction "PA9_30") (pintype "passive"))
    )
    (net (code "77") (name "Net-(STM32JB-PA10)") (class "Default")
      (node (ref "R11") (pin "2") (pinfunction "2_2") (pintype "passive"))
      (node (ref "STM32J") (pin "31") (pinfunction "PA10_31") (pintype "passive"))
    )
    (net (code "78") (name "Net-(USB-DM)") (class "Default")
      (node (ref "R14") (pin "2") (pinfunction "2_2") (pintype "passive"))
      (node (ref "USB") (pin "2") (pinfunction "DM_2") (pintype "passive"))
    )
    (net (code "79") (name "Net-(USB-DP)") (class "Default")
      (node (ref "R12") (pin "2") (pinfunction "2_2") (pintype "passive"))
      (node (ref "R15") (pin "2") (pinfunction "2_2") (pintype "passive"))
      (node (ref "USB") (pin "3") (pinfunction "DP_3") (pintype "passive"))
    )
    (net (code "80") (name "Net-(jUSB-DM)") (class "Default")
      (node (ref "R1") (pin "1") (pinfunction "1_1") (pintype "passive"))
      (node (ref "jUSB") (pin "2") (pinfunction "DM_2") (pintype "passive"))
    )
    (net (code "81") (name "Net-(jUSB-DP)") (class "Default")
      (node (ref "R2") (pin "1") (pinfunction "1_1") (pintype "passive"))
      (node (ref "jUSB") (pin "3") (pinfunction "DP_3") (pintype "passive"))
    )
    (net (code "82") (name "VBAT") (class "Default")
      (node (ref "BATIN") (pin "1") (pinfunction "1_1") (pintype "passive"))
      (node (ref "PW") (pin "3") (pinfunction "3_3") (pintype "passive"))
    )
    (net (code "83") (name "VIN") (class "Default")
      (node (ref "C6") (pin "2") (pinfunction "2_2") (pintype "passive"))
      (node (ref "C7") (pin "2") (pinfunction "2_2") (pintype "passive"))
      (node (ref "PW") (pin "2") (pinfunction "2_2") (pintype "passive"))
      (node (ref "R18") (pin "1") (pinfunction "1_1") (pintype "passive"))
      (node (ref "XC") (pin "3") (pinfunction "IN_3") (pintype "power_in"))
    )
    (net (code "84") (name "VUSB") (class "Default")
      (node (ref "PW") (pin "1") (pinfunction "1_1") (pintype "passive"))
      (node (ref "R13") (pin "2") (pinfunction "2_2") (pintype "passive"))
      (node (ref "USB") (pin "1") (pinfunction "VBUS_1") (pintype "passive"))
      (node (ref "jUSB") (pin "1") (pinfunction "VBUS_1") (pintype "passive"))
    )
    (net (code "85") (name "unconnected-(ICM-FSYNC-Pad8)") (class "Default")
      (node (ref "ICM") (pin "8") (pinfunction "FSYNC_8") (pintype "passive+no_connect"))
    )
    (net (code "86") (name "unconnected-(ICM-RESV-Pad7)") (class "Default")
      (node (ref "ICM") (pin "7") (pinfunction "RESV_7") (pintype "passive+no_connect"))
    )
    (net (code "87") (name "unconnected-(IST-CAD0-Pad5)") (class "Default")
      (node (ref "IST") (pin "5") (pinfunction "CAD0_5") (pintype "passive+no_connect"))
    )
    (net (code "88") (name "unconnected-(IST-CAD1-Pad6)") (class "Default")
      (node (ref "IST") (pin "6") (pinfunction "CAD1_6") (pintype "passive+no_connect"))
    )
    (net (code "89") (name "unconnected-(IST-NC-Pad3)") (class "Default")
      (node (ref "IST") (pin "3") (pinfunction "NC_3") (pintype "passive+no_connect"))
    )
    (net (code "90") (name "unconnected-(IST-RSTN-Pad14)") (class "Default")
      (node (ref "IST") (pin "14") (pinfunction "RSTN_14") (pintype "passive+no_connect"))
    )
    (net (code "91") (name "unconnected-(IST-VPP-Pad7)") (class "Default")
      (node (ref "IST") (pin "7") (pinfunction "VPP_7") (pintype "passive+no_connect"))
    )
    (net (code "92") (name "unconnected-(KEY-Pad3)") (class "Default")
      (node (ref "KEY") (pin "3") (pinfunction "3_3") (pintype "passive+no_connect"))
    )
    (net (code "93") (name "unconnected-(KEY-Pad4)") (class "Default")
      (node (ref "KEY") (pin "4") (pinfunction "4_4") (pintype "passive+no_connect"))
    )
    (net (code "94") (name "unconnected-(STM32JA-OSC_IN-Pad5)") (class "Default")
      (node (ref "STM32J") (pin "5") (pinfunction "OSC_IN_5") (pintype "passive+no_connect"))
    )
    (net (code "95") (name "unconnected-(STM32JA-OSC_OUT-Pad6)") (class "Default")
      (node (ref "STM32J") (pin "6") (pinfunction "OSC_OUT_6") (pintype "passive+no_connect"))
    )
    (net (code "96") (name "unconnected-(STM32JB-PA3-Pad13)") (class "Default")
      (node (ref "STM32J") (pin "13") (pinfunction "PA3_13") (pintype "passive+no_connect"))
    )
    (net (code "97") (name "unconnected-(STM32JB-PA5-Pad15)") (class "Default")
      (node (ref "STM32J") (pin "15") (pinfunction "PA5_15") (pintype "passive+no_connect"))
    )
    (net (code "98") (name "unconnected-(STM32JB-PA6-Pad16)") (class "Default")
      (node (ref "STM32J") (pin "16") (pinfunction "PA6_16") (pintype "passive+no_connect"))
    )
    (net (code "99") (name "unconnected-(STM32JB-PA7-Pad17)") (class "Default")
      (node (ref "STM32J") (pin "17") (pinfunction "PA7_17") (pintype "passive+no_connect"))
    )
    (net (code "100") (name "unconnected-(STM32JB-PA8-Pad29)") (class "Default")
      (node (ref "STM32J") (pin "29") (pinfunction "PA8_29") (pintype "passive+no_connect"))
    )
    (net (code "101") (name "unconnected-(STM32JB-PA15-Pad38)") (class "Default")
      (node (ref "STM32J") (pin "38") (pinfunction "PA15_38") (pintype "passive+no_connect"))
    )
    (net (code "102") (name "unconnected-(STM32JB-PB0-Pad18)") (class "Default")
      (node (ref "STM32J") (pin "18") (pinfunction "PB0_18") (pintype "passive+no_connect"))
    )
    (net (code "103") (name "unconnected-(STM32JB-PB1-Pad19)") (class "Default")
      (node (ref "STM32J") (pin "19") (pinfunction "PB1_19") (pintype "passive+no_connect"))
    )
    (net (code "104") (name "unconnected-(STM32JB-PB2-Pad20)") (class "Default")
      (node (ref "STM32J") (pin "20") (pinfunction "PB2_20") (pintype "passive+no_connect"))
    )
    (net (code "105") (name "unconnected-(STM32JB-PB3-Pad39)") (class "Default")
      (node (ref "STM32J") (pin "39") (pinfunction "PB3_39") (pintype "passive+no_connect"))
    )
    (net (code "106") (name "unconnected-(STM32JB-PB4-Pad40)") (class "Default")
      (node (ref "STM32J") (pin "40") (pinfunction "PB4_40") (pintype "passive+no_connect"))
    )
    (net (code "107") (name "unconnected-(STM32JB-PB5-Pad41)") (class "Default")
      (node (ref "STM32J") (pin "41") (pinfunction "PB5_41") (pintype "passive+no_connect"))
    )
    (net (code "108") (name "unconnected-(STM32JB-PB6-Pad42)") (class "Default")
      (node (ref "STM32J") (pin "42") (pinfunction "PB6_42") (pintype "passive+no_connect"))
    )
    (net (code "109") (name "unconnected-(STM32JB-PB7-Pad43)") (class "Default")
      (node (ref "STM32J") (pin "43") (pinfunction "PB7_43") (pintype "passive+no_connect"))
    )
    (net (code "110") (name "unconnected-(STM32JB-PB8-Pad45)") (class "Default")
      (node (ref "STM32J") (pin "45") (pinfunction "PB8_45") (pintype "passive+no_connect"))
    )
    (net (code "111") (name "unconnected-(STM32JB-PB9-Pad46)") (class "Default")
      (node (ref "STM32J") (pin "46") (pinfunction "PB9_46") (pintype "passive+no_connect"))
    )
    (net (code "112") (name "unconnected-(STM32JB-PB10-Pad21)") (class "Default")
      (node (ref "STM32J") (pin "21") (pinfunction "PB10_21") (pintype "passive+no_connect"))
    )
    (net (code "113") (name "unconnected-(STM32JB-PB11-Pad22)") (class "Default")
      (node (ref "STM32J") (pin "22") (pinfunction "PB11_22") (pintype "passive+no_connect"))
    )
    (net (code "114") (name "unconnected-(STM32JB-PB12-Pad25)") (class "Default")
      (node (ref "STM32J") (pin "25") (pinfunction "PB12_25") (pintype "passive+no_connect"))
    )
    (net (code "115") (name "unconnected-(STM32JB-PB13-Pad26)") (class "Default")
      (node (ref "STM32J") (pin "26") (pinfunction "PB13_26") (pintype "passive+no_connect"))
    )
    (net (code "116") (name "unconnected-(STM32JB-PB14-Pad27)") (class "Default")
      (node (ref "STM32J") (pin "27") (pinfunction "PB14_27") (pintype "passive+no_connect"))
    )
    (net (code "117") (name "unconnected-(STM32JB-PB15-Pad28)") (class "Default")
      (node (ref "STM32J") (pin "28") (pinfunction "PB15_28") (pintype "passive+no_connect"))
    )
    (net (code "118") (name "unconnected-(STM32JB-PC13-Pad2)") (class "Default")
      (node (ref "STM32J") (pin "2") (pinfunction "PC13_2") (pintype "passive+no_connect"))
    )
    (net (code "119") (name "unconnected-(STM32JB-PC14-Pad3)") (class "Default")
      (node (ref "STM32J") (pin "3") (pinfunction "PC14_3") (pintype "passive+no_connect"))
    )
    (net (code "120") (name "unconnected-(STM32JB-PC15-Pad4)") (class "Default")
      (node (ref "STM32J") (pin "4") (pinfunction "PC15_4") (pintype "passive+no_connect"))
    )
    (net (code "121") (name "unconnected-(jUSB-ID-Pad4)") (class "Default")
      (node (ref "jUSB") (pin "4") (pinfunction "ID_4") (pintype "passive+no_connect"))
    )
  )
)
